# Controller.net
KiCad netlist of a schematic drawn in EAGLE
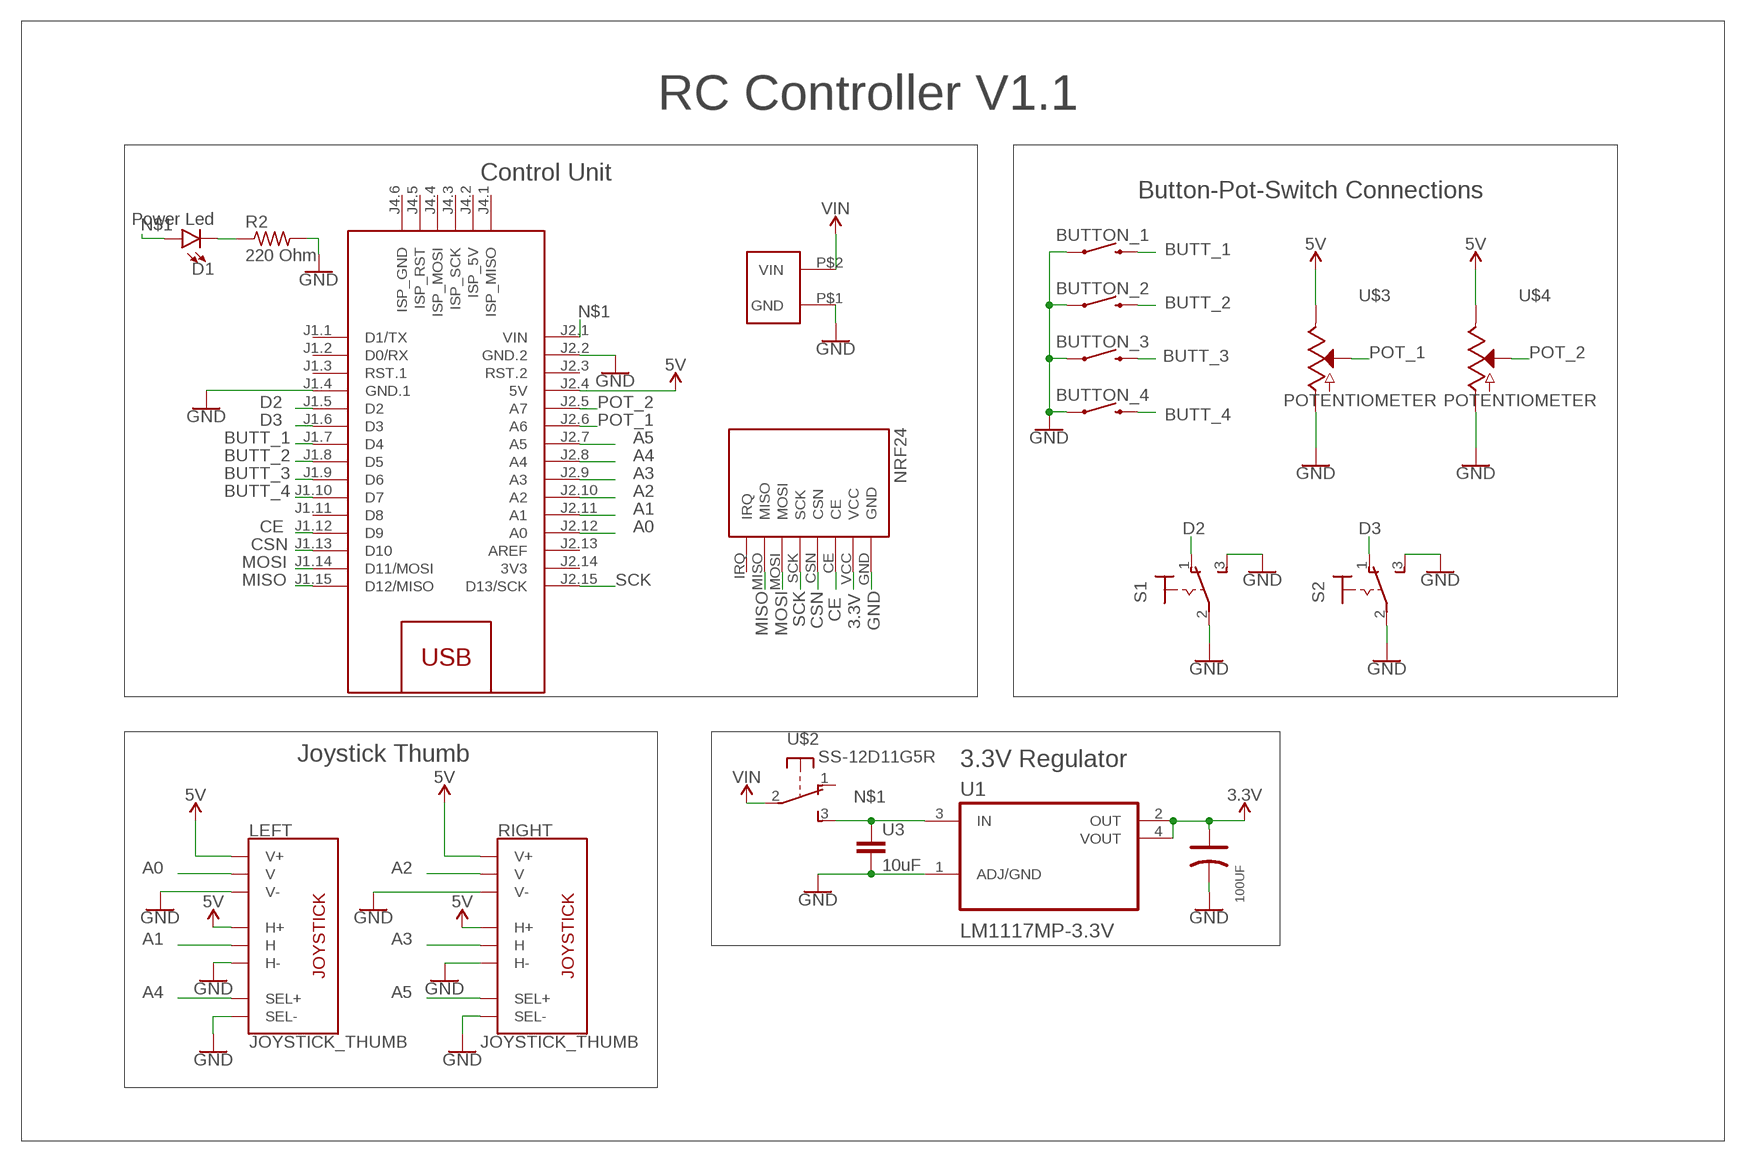
[diagram p0: schematic, sheet 1]

(export (version "E")
  (design (tool "Eeschema 10.0.6"))
  (components
    (comp (ref "BUTTON_1")
      (value "MOMENTARY-SWITCH-SPST-PTH-6.0MM")
      (footprint "eagle-import:TACTILE_SWITCH_PTH_6.0MM")
      (libsource (lib "eagle-import") (part "MOMENTARY-SWITCH-SPST-PTH-6.0MM"))
    )
    (comp (ref "BUTTON_2")
      (value "MOMENTARY-SWITCH-SPST-PTH-6.0MM")
      (footprint "eagle-import:TACTILE_SWITCH_PTH_6.0MM")
      (libsource (lib "eagle-import") (part "MOMENTARY-SWITCH-SPST-PTH-6.0MM"))
    )
    (comp (ref "BUTTON_3")
      (value "MOMENTARY-SWITCH-SPST-PTH-6.0MM")
      (footprint "eagle-import:TACTILE_SWITCH_PTH_6.0MM")
      (libsource (lib "eagle-import") (part "MOMENTARY-SWITCH-SPST-PTH-6.0MM"))
    )
    (comp (ref "BUTTON_4")
      (value "MOMENTARY-SWITCH-SPST-PTH-6.0MM")
      (footprint "eagle-import:TACTILE_SWITCH_PTH_6.0MM")
      (libsource (lib "eagle-import") (part "MOMENTARY-SWITCH-SPST-PTH-6.0MM"))
    )
    (comp (ref "D1")
      (value "Power Led")
      (footprint "eagle-import:LED-1206")
      (libsource (lib "eagle-import") (part "LED-RED1206"))
    )
    (comp (ref "LEFT")
      (value "JOYSTICK_THUMB")
      (footprint "eagle-import:JOYSTICK")
      (libsource (lib "eagle-import") (part "JOYSTICK_THUMB"))
    )
    (comp (ref "M1")
      (value "ARDUINO-NANO-3.0#ISP")
      (footprint "eagle-import:ARDUINO-NANO-3.0#ISP")
      (libsource (lib "eagle-import") (part "ARDUINO-NANO-3.0#ISP"))
    )
    (comp (ref "R2")
      (value "220 Ohm")
      (footprint "eagle-import:RES_1206")
      (fields
        (field (name "DIGIKEY_PART_NUMBER") "P0.0ETR-ND")
        (field (name "MANUFACTURER") "Panasonic Electronic Components")
        (field (name "MPN") "ERJ-8GEY0R00V")
        (field (name "CREATED_BY") "PCBLayout.com")
      )
      (libsource (lib "eagle-import") (part "ERJ-8GEY0R00V"))
    )
    (comp (ref "RIGHT")
      (value "JOYSTICK_THUMB")
      (footprint "eagle-import:JOYSTICK")
      (libsource (lib "eagle-import") (part "JOYSTICK_THUMB"))
    )
    (comp (ref "S1")
      (value "320-916")
      (footprint "eagle-import:320-916")
      (libsource (lib "eagle-import") (part "320-916"))
    )
    (comp (ref "S2")
      (value "320-916")
      (footprint "eagle-import:320-916")
      (libsource (lib "eagle-import") (part "320-916"))
    )
    (comp (ref "U$1")
      (value "VIN")
      (footprint "eagle-import:SMD_VIN")
      (libsource (lib "eagle-import") (part "nrf24_VIN"))
    )
    (comp (ref "U$2")
      (value "SS-12D11G5R")
      (footprint "eagle-import:SWITCH")
      (libsource (lib "eagle-import") (part "SS-12D11G5R"))
    )
    (comp (ref "U$3")
      (value "POTENTIOMETER")
      (footprint "eagle-import:POTENTIOMETER")
      (libsource (lib "eagle-import") (part "POTENTIOMETER"))
    )
    (comp (ref "U$4")
      (value "POTENTIOMETER")
      (footprint "eagle-import:POTENTIOMETER")
      (libsource (lib "eagle-import") (part "POTENTIOMETER"))
    )
    (comp (ref "U$5")
      (value "NRF24")
      (footprint "eagle-import:NRF24")
      (libsource (lib "eagle-import") (part "NRF24"))
    )
    (comp (ref "U1")
      (value "LM1117MP-3.3V")
      (footprint "eagle-import:SOT230P700X180-4N")
      (libsource (lib "eagle-import") (part "LM1117MP-5.0"))
    )
    (comp (ref "U2")
      (value "100UF")
      (footprint "eagle-import:8X10MM")
      (libsource (lib "eagle-import") (part "100UF"))
    )
    (comp (ref "U3")
      (value "10uF")
      (footprint "eagle-import:1206")
      (libsource (lib "eagle-import") (part "10UF-1206-6.3V-20%"))
    )
  )
  (nets
    (net (code "1") (name "/3V3") (class "Default")
      (node (ref "M1") (pin "J2.14") (pinfunction "3V3_J2.14") (pintype "power_in"))
    )
    (net (code "2") (name "/A0") (class "Default")
      (node (ref "LEFT") (pin "V2") (pinfunction "V_V2") (pintype "bidirectional"))
      (node (ref "M1") (pin "J2.12") (pinfunction "A0_J2.12") (pintype "bidirectional"))
    )
    (net (code "3") (name "/A1") (class "Default")
      (node (ref "LEFT") (pin "H2") (pinfunction "H_H2") (pintype "bidirectional"))
      (node (ref "M1") (pin "J2.11") (pinfunction "A1_J2.11") (pintype "bidirectional"))
    )
    (net (code "4") (name "/A2") (class "Default")
      (node (ref "M1") (pin "J2.10") (pinfunction "A2_J2.10") (pintype "bidirectional"))
      (node (ref "RIGHT") (pin "V2") (pinfunction "V_V2") (pintype "bidirectional"))
    )
    (net (code "5") (name "/A3") (class "Default")
      (node (ref "M1") (pin "J2.9") (pinfunction "A3_J2.9") (pintype "bidirectional"))
      (node (ref "RIGHT") (pin "H2") (pinfunction "H_H2") (pintype "bidirectional"))
    )
    (net (code "6") (name "/A4") (class "Default")
      (node (ref "LEFT") (pin "B1A") (pinfunction "SEL+_B1A") (pintype "bidirectional"))
      (node (ref "M1") (pin "J2.8") (pinfunction "A4_J2.8") (pintype "bidirectional"))
    )
    (net (code "7") (name "/A5") (class "Default")
      (node (ref "M1") (pin "J2.7") (pinfunction "A5_J2.7") (pintype "bidirectional"))
      (node (ref "RIGHT") (pin "B1A") (pinfunction "SEL+_B1A") (pintype "bidirectional"))
    )
    (net (code "8") (name "/BUTT_1") (class "Default")
      (node (ref "BUTTON_1") (pin "3") (pinfunction "2_3") (pintype "passive"))
      (node (ref "M1") (pin "J1.7") (pinfunction "D4_J1.7") (pintype "bidirectional"))
    )
    (net (code "9") (name "/BUTT_2") (class "Default")
      (node (ref "BUTTON_2") (pin "3") (pinfunction "2_3") (pintype "passive"))
      (node (ref "M1") (pin "J1.8") (pinfunction "D5_J1.8") (pintype "bidirectional"))
    )
    (net (code "10") (name "/BUTT_3") (class "Default")
      (node (ref "BUTTON_3") (pin "3") (pinfunction "2_3") (pintype "passive"))
      (node (ref "M1") (pin "J1.9") (pinfunction "D6_J1.9") (pintype "bidirectional"))
    )
    (net (code "11") (name "/BUTT_4") (class "Default")
      (node (ref "BUTTON_4") (pin "3") (pinfunction "2_3") (pintype "passive"))
      (node (ref "M1") (pin "J1.10") (pinfunction "D7_J1.10") (pintype "bidirectional"))
    )
    (net (code "12") (name "/CE") (class "Default")
      (node (ref "M1") (pin "J1.12") (pinfunction "D9_J1.12") (pintype "bidirectional"))
      (node (ref "U$5") (pin "CE") (pinfunction "CE_CE") (pintype "bidirectional"))
    )
    (net (code "13") (name "/CSN") (class "Default")
      (node (ref "M1") (pin "J1.13") (pinfunction "D10_J1.13") (pintype "bidirectional"))
      (node (ref "U$5") (pin "CSN") (pinfunction "CSN_CSN") (pintype "bidirectional"))
    )
    (net (code "14") (name "/D2") (class "Default")
      (node (ref "M1") (pin "J1.5") (pinfunction "D2_J1.5") (pintype "bidirectional"))
      (node (ref "S1") (pin "1") (pinfunction "O_1") (pintype "passive"))
    )
    (net (code "15") (name "/D3") (class "Default")
      (node (ref "M1") (pin "J1.6") (pinfunction "D3_J1.6") (pintype "bidirectional"))
      (node (ref "S2") (pin "1") (pinfunction "O_1") (pintype "passive"))
    )
    (net (code "16") (name "/MISO") (class "Default")
      (node (ref "M1") (pin "J1.15") (pinfunction "D12/MISO_J1.15") (pintype "bidirectional"))
      (node (ref "U$5") (pin "MISO") (pinfunction "MISO_MISO") (pintype "bidirectional"))
    )
    (net (code "17") (name "/MOSI") (class "Default")
      (node (ref "M1") (pin "J1.14") (pinfunction "D11/MOSI_J1.14") (pintype "bidirectional"))
      (node (ref "U$5") (pin "MOSI") (pinfunction "MOSI_MOSI") (pintype "bidirectional"))
    )
    (net (code "18") (name "/N$1") (class "Default")
      (node (ref "D1") (pin "A") (pinfunction "A_A") (pintype "passive"))
      (node (ref "M1") (pin "J2.1") (pinfunction "VIN_J2.1") (pintype "power_in"))
      (node (ref "U$2") (pin "3") (pinfunction "S_3") (pintype "passive"))
      (node (ref "U1") (pin "3") (pinfunction "IN_3") (pintype "input"))
      (node (ref "U3") (pin "1") (pinfunction "1_1") (pintype "passive"))
    )
    (net (code "19") (name "/POT_1") (class "Default")
      (node (ref "M1") (pin "J2.6") (pinfunction "A6_J2.6") (pintype "bidirectional"))
      (node (ref "U$3") (pin "2") (pinfunction "2_2") (pintype "passive"))
    )
    (net (code "20") (name "/POT_2") (class "Default")
      (node (ref "M1") (pin "J2.5") (pinfunction "A7_J2.5") (pintype "bidirectional"))
      (node (ref "U$4") (pin "2") (pinfunction "2_2") (pintype "passive"))
    )
    (net (code "21") (name "/SCK") (class "Default")
      (node (ref "M1") (pin "J2.15") (pinfunction "D13/SCK_J2.15") (pintype "bidirectional"))
      (node (ref "U$5") (pin "SCK") (pinfunction "SCK_SCK") (pintype "bidirectional"))
    )
    (net (code "22") (name "3.3V") (class "Default")
      (node (ref "U$5") (pin "VCC") (pinfunction "VCC_VCC") (pintype "bidirectional"))
      (node (ref "U1") (pin "2") (pinfunction "OUT_2") (pintype "output"))
      (node (ref "U1") (pin "4") (pinfunction "VOUT_4") (pintype "output"))
      (node (ref "U2") (pin "1") (pinfunction "+_1") (pintype "passive"))
    )
    (net (code "23") (name "5V") (class "Default")
      (node (ref "LEFT") (pin "H1") (pinfunction "H+_H1") (pintype "bidirectional"))
      (node (ref "LEFT") (pin "V1") (pinfunction "V+_V1") (pintype "bidirectional"))
      (node (ref "M1") (pin "J2.4") (pinfunction "5V_J2.4") (pintype "power_in"))
      (node (ref "RIGHT") (pin "H1") (pinfunction "H+_H1") (pintype "bidirectional"))
      (node (ref "RIGHT") (pin "V1") (pinfunction "V+_V1") (pintype "bidirectional"))
      (node (ref "U$3") (pin "1") (pinfunction "1_1") (pintype "passive"))
      (node (ref "U$4") (pin "1") (pinfunction "1_1") (pintype "passive"))
    )
    (net (code "24") (name "GND") (class "Default")
      (node (ref "BUTTON_1") (pin "1") (pinfunction "1_1") (pintype "passive"))
      (node (ref "BUTTON_2") (pin "1") (pinfunction "1_1") (pintype "passive"))
      (node (ref "BUTTON_3") (pin "1") (pinfunction "1_1") (pintype "passive"))
      (node (ref "BUTTON_4") (pin "1") (pinfunction "1_1") (pintype "passive"))
      (node (ref "LEFT") (pin "B2A") (pinfunction "SEL-_B2A") (pintype "bidirectional"))
      (node (ref "LEFT") (pin "H3") (pinfunction "H-_H3") (pintype "bidirectional"))
      (node (ref "LEFT") (pin "V3") (pinfunction "V-_V3") (pintype "bidirectional"))
      (node (ref "M1") (pin "J1.4") (pinfunction "GND.1_J1.4") (pintype "power_in"))
      (node (ref "M1") (pin "J2.2") (pinfunction "GND.2_J2.2") (pintype "power_in"))
      (node (ref "R2") (pin "2") (pinfunction "2_2") (pintype "passive"))
      (node (ref "RIGHT") (pin "B2A") (pinfunction "SEL-_B2A") (pintype "bidirectional"))
      (node (ref "RIGHT") (pin "H3") (pinfunction "H-_H3") (pintype "bidirectional"))
      (node (ref "RIGHT") (pin "V3") (pinfunction "V-_V3") (pintype "bidirectional"))
      (node (ref "S1") (pin "2") (pinfunction "P_2") (pintype "passive"))
      (node (ref "S1") (pin "3") (pinfunction "S_3") (pintype "passive"))
      (node (ref "S2") (pin "2") (pinfunction "P_2") (pintype "passive"))
      (node (ref "S2") (pin "3") (pinfunction "S_3") (pintype "passive"))
      (node (ref "U$1") (pin "P$1") (pinfunction "GND_P$1") (pintype "bidirectional"))
      (node (ref "U$3") (pin "3") (pinfunction "3_3") (pintype "passive"))
      (node (ref "U$4") (pin "3") (pinfunction "3_3") (pintype "passive"))
      (node (ref "U$5") (pin "GND") (pinfunction "GND_GND") (pintype "bidirectional"))
      (node (ref "U1") (pin "1") (pinfunction "ADJ/GND_1") (pintype "bidirectional"))
      (node (ref "U2") (pin "2") (pinfunction "-_2") (pintype "passive"))
      (node (ref "U3") (pin "2") (pinfunction "2_2") (pintype "passive"))
    )
    (net (code "25") (name "Net-(D1-PadC)") (class "Default")
      (node (ref "D1") (pin "C") (pinfunction "C_C") (pintype "passive"))
      (node (ref "R2") (pin "1") (pinfunction "1_1") (pintype "passive"))
    )
    (net (code "26") (name "VIN") (class "Default")
      (node (ref "U$1") (pin "P$2") (pinfunction "VIN_P$2") (pintype "bidirectional"))
      (node (ref "U$2") (pin "2") (pinfunction "P_2") (pintype "passive"))
    )
    (net (code "27") (name "unconnected-(M1-AREF-PadJ2.13)") (class "Default")
      (node (ref "M1") (pin "J2.13") (pinfunction "AREF_J2.13") (pintype "bidirectional"))
    )
    (net (code "28") (name "unconnected-(M1-D0{slash}RX-PadJ1.2)") (class "Default")
      (node (ref "M1") (pin "J1.2") (pinfunction "D0/RX_J1.2") (pintype "bidirectional"))
    )
    (net (code "29") (name "unconnected-(M1-D1{slash}TX-PadJ1.1)") (class "Default")
      (node (ref "M1") (pin "J1.1") (pinfunction "D1/TX_J1.1") (pintype "bidirectional"))
    )
    (net (code "30") (name "unconnected-(M1-D8-PadJ1.11)") (class "Default")
      (node (ref "M1") (pin "J1.11") (pinfunction "D8_J1.11") (pintype "bidirectional"))
    )
    (net (code "31") (name "unconnected-(M1-ISP_5V-PadJ4.2)") (class "Default")
      (node (ref "M1") (pin "J4.2") (pinfunction "ISP_5V_J4.2") (pintype "bidirectional"))
    )
    (net (code "32") (name "unconnected-(M1-ISP_GND-PadJ4.6)") (class "Default")
      (node (ref "M1") (pin "J4.6") (pinfunction "ISP_GND_J4.6") (pintype "bidirectional"))
    )
    (net (code "33") (name "unconnected-(M1-ISP_MISO-PadJ4.1)") (class "Default")
      (node (ref "M1") (pin "J4.1") (pinfunction "ISP_MISO_J4.1") (pintype "bidirectional"))
    )
    (net (code "34") (name "unconnected-(M1-ISP_MOSI-PadJ4.4)") (class "Default")
      (node (ref "M1") (pin "J4.4") (pinfunction "ISP_MOSI_J4.4") (pintype "bidirectional"))
    )
    (net (code "35") (name "unconnected-(M1-ISP_RST-PadJ4.5)") (class "Default")
      (node (ref "M1") (pin "J4.5") (pinfunction "ISP_RST_J4.5") (pintype "bidirectional"))
    )
    (net (code "36") (name "unconnected-(M1-ISP_SCK-PadJ4.3)") (class "Default")
      (node (ref "M1") (pin "J4.3") (pinfunction "ISP_SCK_J4.3") (pintype "bidirectional"))
    )
    (net (code "37") (name "unconnected-(M1-RST.1-PadJ1.3)") (class "Default")
      (node (ref "M1") (pin "J1.3") (pinfunction "RST.1_J1.3") (pintype "bidirectional"))
    )
    (net (code "38") (name "unconnected-(M1-RST.2-PadJ2.3)") (class "Default")
      (node (ref "M1") (pin "J2.3") (pinfunction "RST.2_J2.3") (pintype "bidirectional"))
    )
    (net (code "39") (name "unconnected-(U$2-O-Pad1)") (class "Default")
      (node (ref "U$2") (pin "1") (pinfunction "O_1") (pintype "passive"))
    )
    (net (code "40") (name "unconnected-(U$5-PadIRQ)") (class "Default")
      (node (ref "U$5") (pin "IRQ") (pinfunction "IRQ_IRQ") (pintype "bidirectional"))
    )
  )
)
